# analog-daughter-as-built.net
KiCad netlist of a schematic drawn in EAGLE
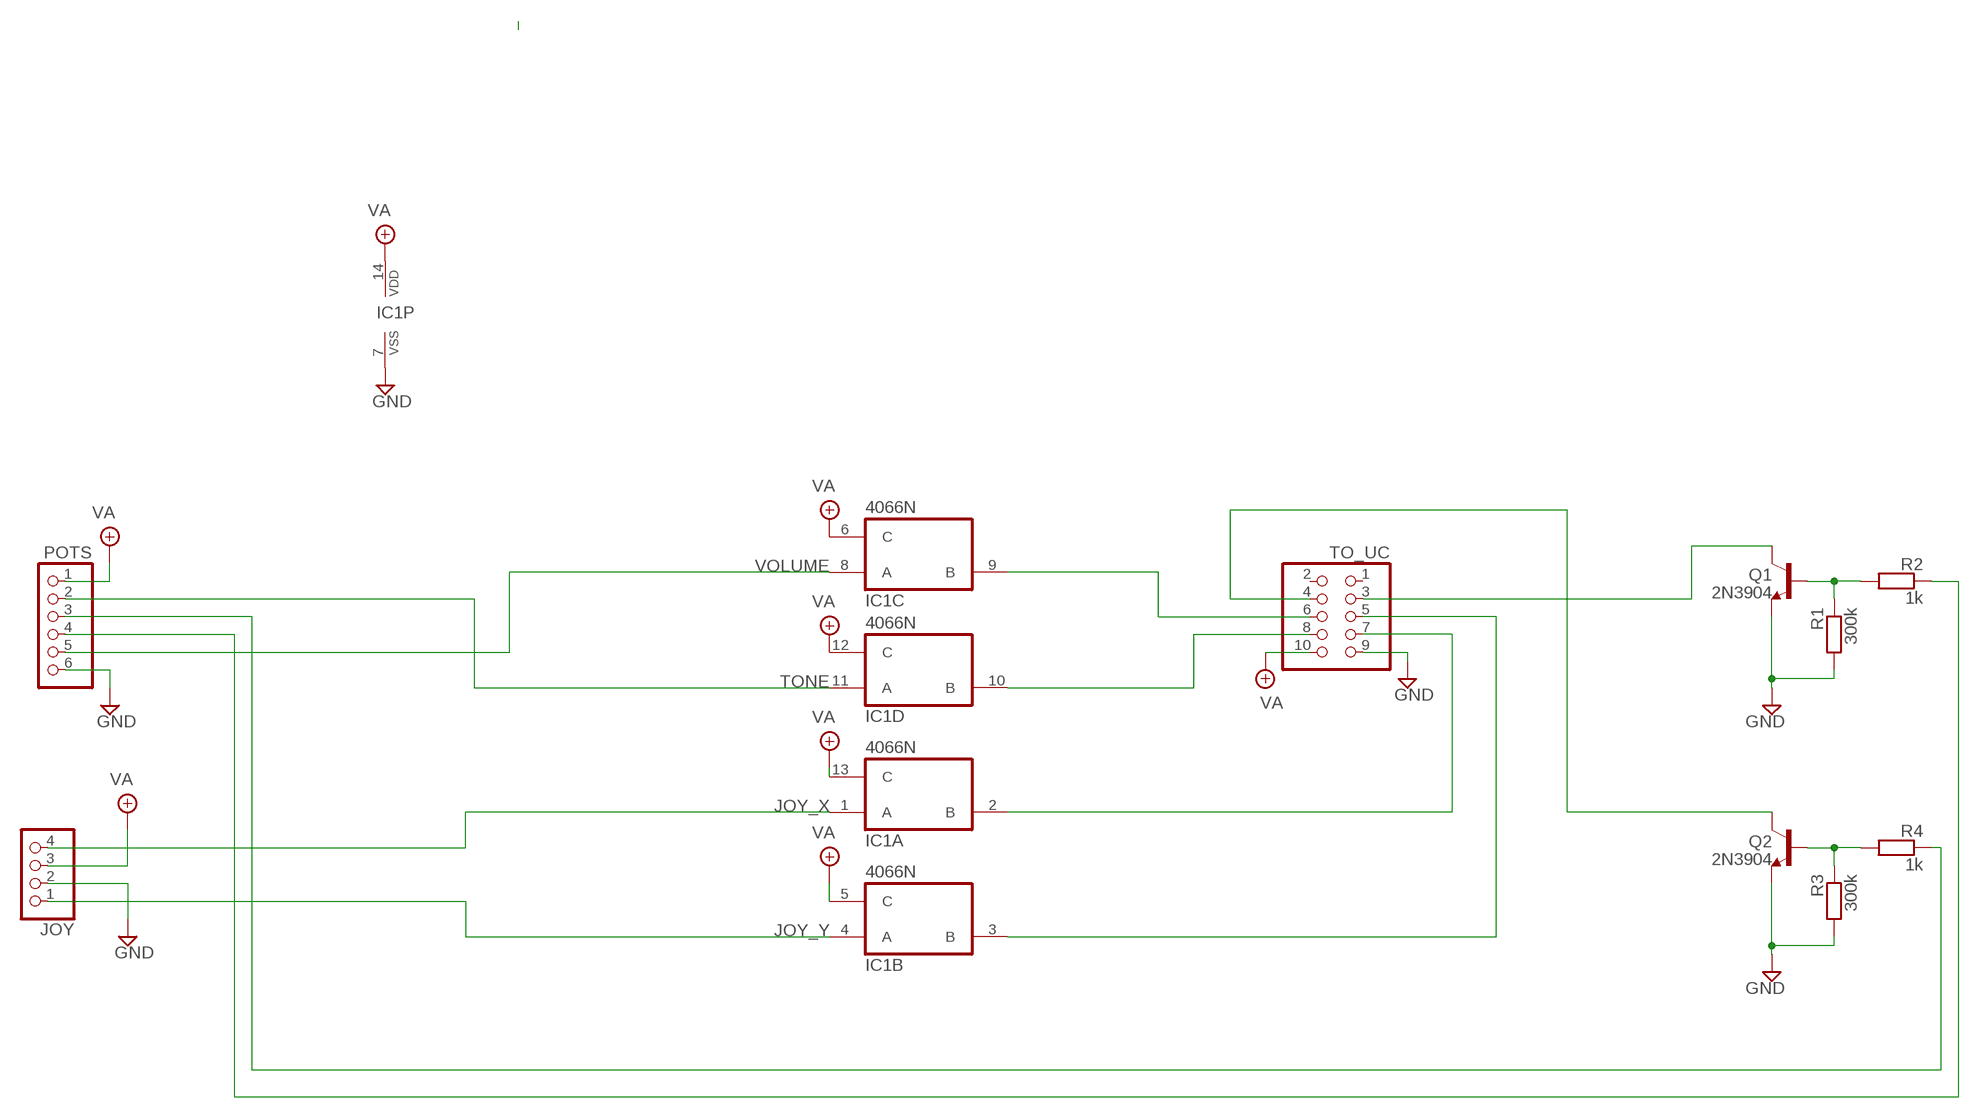
[diagram p0: schematic, sheet 1]

(export (version "E")
  (design (tool "Eeschema 10.0.6"))
  (components
    (comp (ref "IC1")
      (value "4066N")
      (footprint "eagle-import:DIL14")
      (libsource (lib "eagle-import") (part "4066N"))
    )
    (comp (ref "JOY")
      (value "PINHD-1X4")
      (footprint "eagle-import:1X04")
      (libsource (lib "eagle-import") (part "PINHD-1X4"))
    )
    (comp (ref "POTS")
      (value "PINHD-1X6")
      (footprint "eagle-import:1X06")
      (libsource (lib "eagle-import") (part "PINHD-1X6"))
    )
    (comp (ref "Q1")
      (value "2N3904")
      (footprint "eagle-import:TO92-")
      (libsource (lib "eagle-import") (part "2N3904"))
    )
    (comp (ref "Q2")
      (value "2N3904")
      (footprint "eagle-import:TO92-")
      (libsource (lib "eagle-import") (part "2N3904"))
    )
    (comp (ref "R1")
      (value "300k")
      (footprint "eagle-import:R0207_1V")
      (libsource (lib "eagle-import") (part "6MM-EU1"))
    )
    (comp (ref "R2")
      (value "1k")
      (footprint "eagle-import:R0207_1V")
      (libsource (lib "eagle-import") (part "6MM-EU1"))
    )
    (comp (ref "R3")
      (value "300k")
      (footprint "eagle-import:R0207_1V")
      (libsource (lib "eagle-import") (part "6MM-EU1"))
    )
    (comp (ref "R4")
      (value "1k")
      (footprint "eagle-import:R0207_1V")
      (libsource (lib "eagle-import") (part "6MM-EU1"))
    )
    (comp (ref "TO_UC")
      (value "PINHD-2X5")
      (footprint "eagle-import:2X05")
      (libsource (lib "eagle-import") (part "PINHD-2X5"))
    )
  )
  (nets
    (net (code "1") (name "/JOY_X") (class "Default")
      (node (ref "IC1") (pin "1") (pinfunction "A_1") (pintype "tri_state"))
      (node (ref "JOY") (pin "4") (pinfunction "4_4") (pintype "passive"))
    )
    (net (code "2") (name "/JOY_Y") (class "Default")
      (node (ref "IC1") (pin "4") (pinfunction "A_4") (pintype "tri_state"))
      (node (ref "JOY") (pin "1") (pinfunction "1_1") (pintype "passive"))
    )
    (net (code "3") (name "/TONE") (class "Default")
      (node (ref "IC1") (pin "11") (pinfunction "A_11") (pintype "tri_state"))
      (node (ref "POTS") (pin "2") (pinfunction "2_2") (pintype "passive"))
    )
    (net (code "4") (name "/VOLUME") (class "Default")
      (node (ref "IC1") (pin "8") (pinfunction "A_8") (pintype "tri_state"))
      (node (ref "POTS") (pin "5") (pinfunction "5_5") (pintype "passive"))
    )
    (net (code "5") (name "GND") (class "Default")
      (node (ref "IC1") (pin "7") (pinfunction "VSS_7") (pintype "power_in"))
      (node (ref "JOY") (pin "2") (pinfunction "2_2") (pintype "passive"))
      (node (ref "POTS") (pin "6") (pinfunction "6_6") (pintype "passive"))
      (node (ref "Q1") (pin "3") (pinfunction "E_3") (pintype "passive"))
      (node (ref "Q2") (pin "3") (pinfunction "E_3") (pintype "passive"))
      (node (ref "R1") (pin "2") (pinfunction "2_2") (pintype "passive"))
      (node (ref "R3") (pin "2") (pinfunction "2_2") (pintype "passive"))
      (node (ref "TO_UC") (pin "9") (pinfunction "9_9") (pintype "passive"))
    )
    (net (code "6") (name "Net-(IC1A-B)") (class "Default")
      (node (ref "IC1") (pin "2") (pinfunction "B_2") (pintype "tri_state"))
      (node (ref "TO_UC") (pin "7") (pinfunction "7_7") (pintype "passive"))
    )
    (net (code "7") (name "Net-(IC1B-B)") (class "Default")
      (node (ref "IC1") (pin "3") (pinfunction "B_3") (pintype "tri_state"))
      (node (ref "TO_UC") (pin "5") (pinfunction "5_5") (pintype "passive"))
    )
    (net (code "8") (name "Net-(IC1C-B)") (class "Default")
      (node (ref "IC1") (pin "9") (pinfunction "B_9") (pintype "tri_state"))
      (node (ref "TO_UC") (pin "6") (pinfunction "6_6") (pintype "passive"))
    )
    (net (code "9") (name "Net-(IC1D-B)") (class "Default")
      (node (ref "IC1") (pin "10") (pinfunction "B_10") (pintype "tri_state"))
      (node (ref "TO_UC") (pin "8") (pinfunction "8_8") (pintype "passive"))
    )
    (net (code "10") (name "Net-(POTS-Pad3)") (class "Default")
      (node (ref "POTS") (pin "3") (pinfunction "3_3") (pintype "passive"))
      (node (ref "R4") (pin "1") (pinfunction "1_1") (pintype "passive"))
    )
    (net (code "11") (name "Net-(POTS-Pad4)") (class "Default")
      (node (ref "POTS") (pin "4") (pinfunction "4_4") (pintype "passive"))
      (node (ref "R2") (pin "1") (pinfunction "1_1") (pintype "passive"))
    )
    (net (code "12") (name "Net-(Q1-B)") (class "Default")
      (node (ref "Q1") (pin "2") (pinfunction "B_2") (pintype "passive"))
      (node (ref "R1") (pin "1") (pinfunction "1_1") (pintype "passive"))
      (node (ref "R2") (pin "2") (pinfunction "2_2") (pintype "passive"))
    )
    (net (code "13") (name "Net-(Q1-C)") (class "Default")
      (node (ref "Q1") (pin "1") (pinfunction "C_1") (pintype "passive"))
      (node (ref "TO_UC") (pin "3") (pinfunction "3_3") (pintype "passive"))
    )
    (net (code "14") (name "Net-(Q2-B)") (class "Default")
      (node (ref "Q2") (pin "2") (pinfunction "B_2") (pintype "passive"))
      (node (ref "R3") (pin "1") (pinfunction "1_1") (pintype "passive"))
      (node (ref "R4") (pin "2") (pinfunction "2_2") (pintype "passive"))
    )
    (net (code "15") (name "Net-(Q2-C)") (class "Default")
      (node (ref "Q2") (pin "1") (pinfunction "C_1") (pintype "passive"))
      (node (ref "TO_UC") (pin "4") (pinfunction "4_4") (pintype "passive"))
    )
    (net (code "16") (name "VA") (class "Default")
      (node (ref "IC1") (pin "12") (pinfunction "C_12") (pintype "input"))
      (node (ref "IC1") (pin "13") (pinfunction "C_13") (pintype "input"))
      (node (ref "IC1") (pin "14") (pinfunction "VDD_14") (pintype "power_in"))
      (node (ref "IC1") (pin "5") (pinfunction "C_5") (pintype "input"))
      (node (ref "IC1") (pin "6") (pinfunction "C_6") (pintype "input"))
      (node (ref "JOY") (pin "3") (pinfunction "3_3") (pintype "passive"))
      (node (ref "POTS") (pin "1") (pinfunction "1_1") (pintype "passive"))
      (node (ref "TO_UC") (pin "10") (pinfunction "10_10") (pintype "passive"))
    )
    (net (code "17") (name "unconnected-(TO_UC-Pad1)") (class "Default")
      (node (ref "TO_UC") (pin "1") (pinfunction "1_1") (pintype "passive"))
    )
    (net (code "18") (name "unconnected-(TO_UC-Pad2)") (class "Default")
      (node (ref "TO_UC") (pin "2") (pinfunction "2_2") (pintype "passive"))
    )
  )
)
